# PSCLK.net
KiCad netlist of a schematic drawn in Altium Designer
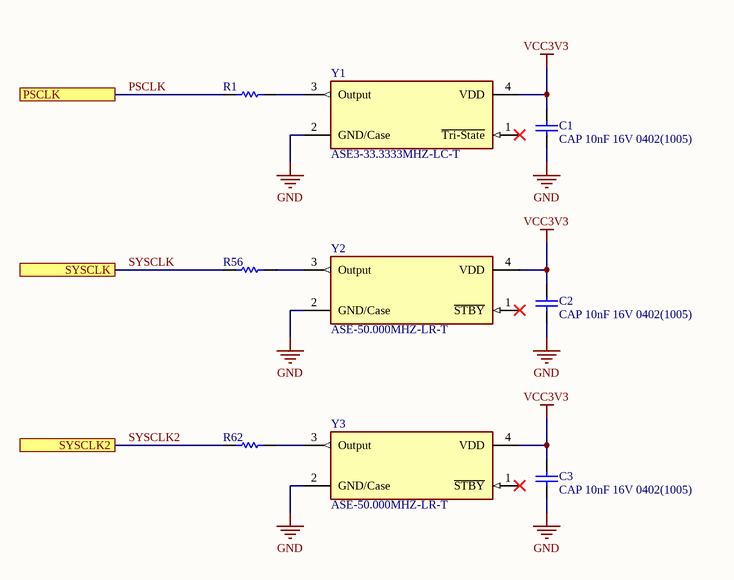
[diagram p0: PSCLK.SchDoc]

(export (version "E")
  (design (tool "Eeschema 10.0.6"))
  (components
    (comp (ref "C1")
      (value "CAP 10nF 16V 0402(1005)")
      (footprint "CAPC0402(1005)60_M")
      (description "CAP 10nF 16V -20% to +80% 0402 (1005 Metric) Thickness 0.6mm SMD")
      (fields (field (name "TOLERANCE") "-20% to +80%"))
      (libsource (lib "Altium Content Vault") (part "CAP"))
    )
    (comp (ref "C2")
      (value "CAP 10nF 16V 0402(1005)")
      (footprint "CAPC0402(1005)60_M")
      (description "CAP 10nF 16V -20% to +80% 0402 (1005 Metric) Thickness 0.6mm SMD")
      (fields (field (name "TOLERANCE") "-20% to +80%"))
      (libsource (lib "Altium Content Vault") (part "CAP"))
    )
    (comp (ref "C3")
      (value "CAP 10nF 16V 0402(1005)")
      (footprint "CAPC0402(1005)60_M")
      (description "CAP 10nF 16V -20% to +80% 0402 (1005 Metric) Thickness 0.6mm SMD")
      (fields (field (name "TOLERANCE") "-20% to +80%"))
      (libsource (lib "Altium Content Vault") (part "CAP"))
    )
    (comp (ref "R1")
      (value "ERJ2RKF33R0X")
      (footprint "RESC1005X40X25LL05T05")
      (fields (field (name "MANUFACTURER") "Panasonic"))
      (libsource (lib "Altium Content Vault") (part "RES"))
    )
    (comp (ref "R56")
      (value "ERJ2RKF33R0X")
      (footprint "RESC1005X40X25LL05T05")
      (fields (field (name "MANUFACTURER") "Panasonic"))
      (libsource (lib "Altium Content Vault") (part "RES"))
    )
    (comp (ref "R62")
      (value "ERJ2RKF33R0X")
      (footprint "RESC1005X40X25LL05T05")
      (fields (field (name "MANUFACTURER") "Panasonic"))
      (libsource (lib "Altium Content Vault") (part "RES"))
    )
    (comp (ref "Y1")
      (value "ASE3-33.3333MHZ-LC-T")
      (footprint "FP-ASE3-MFG")
      (description "XTAL Oscillator 33.3333MHz ±50ppm CMOS 1.8V 4-SMD 3.2mm x 2.5mm")
      (libsource (lib "Altium Content Vault") (part "37c4c26fe5ae6223af2046a137c0b30"))
    )
    (comp (ref "Y2")
      (value "ASE-50.000MHZ-LR-T")
      (footprint "FP-ASE-MFG")
      (description "XTAL Oscillator 50MHz ±25ppm CMOS 3.3V 4-SMD 3.2mm x 2.5mm")
      (libsource (lib "Altium Content Vault") (part "61a724e6190563596ac712fef61ad37"))
    )
    (comp (ref "Y3")
      (value "ASE-50.000MHZ-LR-T")
      (footprint "FP-ASE-MFG")
      (description "XTAL Oscillator 50MHz ±25ppm CMOS 3.3V 4-SMD 3.2mm x 2.5mm")
      (libsource (lib "Altium Content Vault") (part "61a724e6190563596ac712fef61ad37"))
    )
  )
  (nets
    (net (code "1") (name "/PSCLK") (class "Default")
      (node (ref "R1") (pin "1") (pinfunction "1_1") (pintype "passive"))
    )
    (net (code "2") (name "/SYSCLK") (class "Default")
      (node (ref "R56") (pin "1") (pinfunction "1_1") (pintype "passive"))
    )
    (net (code "3") (name "/SYSCLK2") (class "Default")
      (node (ref "R62") (pin "1") (pinfunction "1_1") (pintype "passive"))
    )
    (net (code "4") (name "GND") (class "Default")
      (node (ref "C1") (pin "1") (pinfunction "1_1") (pintype "passive"))
      (node (ref "C2") (pin "1") (pinfunction "1_1") (pintype "passive"))
      (node (ref "C3") (pin "1") (pinfunction "1_1") (pintype "passive"))
      (node (ref "Y1") (pin "2") (pinfunction "GND/Case_2") (pintype "power_in"))
      (node (ref "Y2") (pin "2") (pinfunction "GND/Case_2") (pintype "power_in"))
      (node (ref "Y3") (pin "2") (pinfunction "GND/Case_2") (pintype "power_in"))
    )
    (net (code "5") (name "Net-(Y1-Output)") (class "Default")
      (node (ref "R1") (pin "2") (pinfunction "2_2") (pintype "passive"))
      (node (ref "Y1") (pin "3") (pinfunction "Output_3") (pintype "output"))
    )
    (net (code "6") (name "Net-(Y2-Output)") (class "Default")
      (node (ref "R56") (pin "2") (pinfunction "2_2") (pintype "passive"))
      (node (ref "Y2") (pin "3") (pinfunction "Output_3") (pintype "output"))
    )
    (net (code "7") (name "Net-(Y3-Output)") (class "Default")
      (node (ref "R62") (pin "2") (pinfunction "2_2") (pintype "passive"))
      (node (ref "Y3") (pin "3") (pinfunction "Output_3") (pintype "output"))
    )
    (net (code "8") (name "VCC3V3") (class "Default")
      (node (ref "C1") (pin "2") (pinfunction "2_2") (pintype "passive"))
      (node (ref "C2") (pin "2") (pinfunction "2_2") (pintype "passive"))
      (node (ref "C3") (pin "2") (pinfunction "2_2") (pintype "passive"))
      (node (ref "Y1") (pin "4") (pinfunction "VDD_4") (pintype "power_in"))
      (node (ref "Y2") (pin "4") (pinfunction "VDD_4") (pintype "power_in"))
      (node (ref "Y3") (pin "4") (pinfunction "VDD_4") (pintype "power_in"))
    )
    (net (code "9") (name "unconnected-(Y1-~{Tri-State}-Pad1)") (class "Default")
      (node (ref "Y1") (pin "1") (pinfunction "~{Tri-State}_1") (pintype "input+no_connect"))
    )
    (net (code "10") (name "unconnected-(Y2-~{STBY}-Pad1)") (class "Default")
      (node (ref "Y2") (pin "1") (pinfunction "~{STBY}_1") (pintype "input+no_connect"))
    )
    (net (code "11") (name "unconnected-(Y3-~{STBY}-Pad1)") (class "Default")
      (node (ref "Y3") (pin "1") (pinfunction "~{STBY}_1") (pintype "input+no_connect"))
    )
  )
)
